# 5V_Inputs.net
KiCad netlist of a schematic drawn in Altium Designer
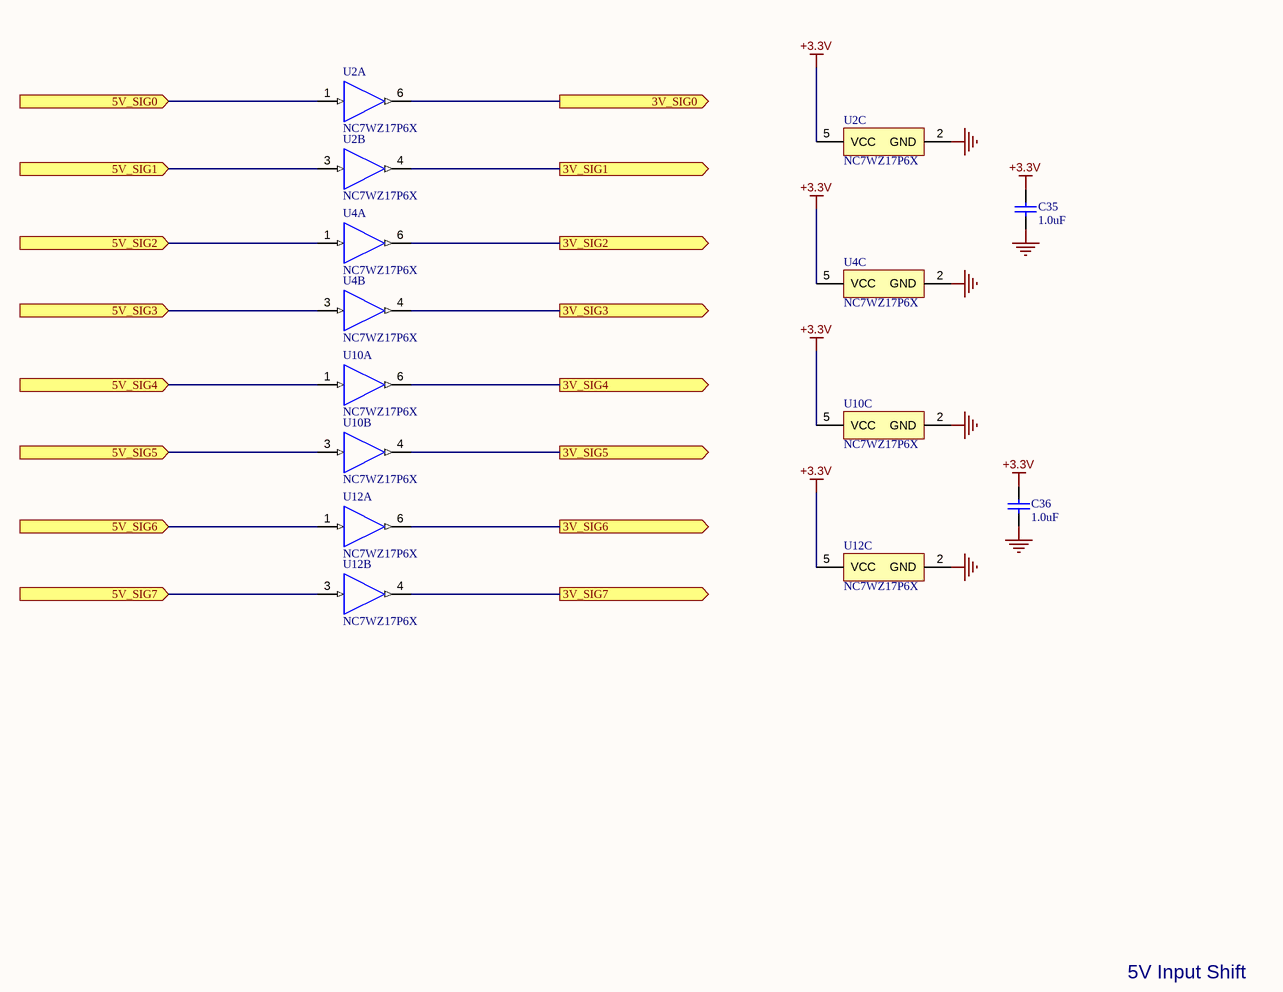
[diagram p0: 5V_Inputs.SchDoc]

(export (version "E")
  (design (tool "Eeschema 10.0.6"))
  (components
    (comp (ref "C35")
      (value "1.0uF")
      (footprint "0402_C")
      (description "Chip capacitor")
      (fields
        (field (name "MANUFACTURER") "Samsung Electro-Mechanics")
        (field (name "PARTNUMBER") "CL05A105KA5NQNC")
      )
      (libsource (lib "Cap") (part "0402 1.0uF (105) 10% 25V"))
    )
    (comp (ref "C36")
      (value "1.0uF")
      (footprint "0402_C")
      (description "Chip capacitor")
      (fields
        (field (name "MANUFACTURER") "Samsung Electro-Mechanics")
        (field (name "PARTNUMBER") "CL05A105KA5NQNC")
      )
      (libsource (lib "Cap") (part "0402 1.0uF (105) 10% 25V"))
    )
    (comp (ref "U2")
      (value "NC7WZ17P6X")
      (footprint "FAIR-SC70-6_V")
      (fields (field (name "MANUFACTURER") "Fairchild Semiconductor"))
      (libsource (lib "Altium Content Vault") (part "BUFFER-2-1IN-6"))
    )
    (comp (ref "U4")
      (value "NC7WZ17P6X")
      (footprint "FAIR-SC70-6_V")
      (fields (field (name "MANUFACTURER") "Fairchild Semiconductor"))
      (libsource (lib "Altium Content Vault") (part "BUFFER-2-1IN-6"))
    )
    (comp (ref "U10")
      (value "NC7WZ17P6X")
      (footprint "FAIR-SC70-6_V")
      (fields (field (name "MANUFACTURER") "Fairchild Semiconductor"))
      (libsource (lib "Altium Content Vault") (part "BUFFER-2-1IN-6"))
    )
    (comp (ref "U12")
      (value "NC7WZ17P6X")
      (footprint "FAIR-SC70-6_V")
      (fields (field (name "MANUFACTURER") "Fairchild Semiconductor"))
      (libsource (lib "Altium Content Vault") (part "BUFFER-2-1IN-6"))
    )
  )
  (nets
    (net (code "1") (name "+3.3V") (class "Default")
      (node (ref "C35") (pin "1") (pinfunction "1_1") (pintype "passive"))
      (node (ref "C36") (pin "1") (pinfunction "1_1") (pintype "passive"))
      (node (ref "U10") (pin "5") (pinfunction "VCC_5") (pintype "power_in"))
      (node (ref "U12") (pin "5") (pinfunction "VCC_5") (pintype "power_in"))
      (node (ref "U2") (pin "5") (pinfunction "VCC_5") (pintype "power_in"))
      (node (ref "U4") (pin "5") (pinfunction "VCC_5") (pintype "power_in"))
    )
    (net (code "2") (name "/3V_SIG0") (class "Default")
      (node (ref "U2") (pin "6") (pinfunction "Y1_6") (pintype "output"))
    )
    (net (code "3") (name "/3V_SIG1") (class "Default")
      (node (ref "U2") (pin "4") (pinfunction "Y2_4") (pintype "output"))
    )
    (net (code "4") (name "/3V_SIG2") (class "Default")
      (node (ref "U4") (pin "6") (pinfunction "Y1_6") (pintype "output"))
    )
    (net (code "5") (name "/3V_SIG3") (class "Default")
      (node (ref "U4") (pin "4") (pinfunction "Y2_4") (pintype "output"))
    )
    (net (code "6") (name "/3V_SIG4") (class "Default")
      (node (ref "U10") (pin "6") (pinfunction "Y1_6") (pintype "output"))
    )
    (net (code "7") (name "/3V_SIG5") (class "Default")
      (node (ref "U10") (pin "4") (pinfunction "Y2_4") (pintype "output"))
    )
    (net (code "8") (name "/3V_SIG6") (class "Default")
      (node (ref "U12") (pin "6") (pinfunction "Y1_6") (pintype "output"))
    )
    (net (code "9") (name "/3V_SIG7") (class "Default")
      (node (ref "U12") (pin "4") (pinfunction "Y2_4") (pintype "output"))
    )
    (net (code "10") (name "/5V_SIG0") (class "Default")
      (node (ref "U2") (pin "1") (pinfunction "A1_1") (pintype "input"))
    )
    (net (code "11") (name "/5V_SIG1") (class "Default")
      (node (ref "U2") (pin "3") (pinfunction "A2_3") (pintype "input"))
    )
    (net (code "12") (name "/5V_SIG2") (class "Default")
      (node (ref "U4") (pin "1") (pinfunction "A1_1") (pintype "input"))
    )
    (net (code "13") (name "/5V_SIG3") (class "Default")
      (node (ref "U4") (pin "3") (pinfunction "A2_3") (pintype "input"))
    )
    (net (code "14") (name "/5V_SIG4") (class "Default")
      (node (ref "U10") (pin "1") (pinfunction "A1_1") (pintype "input"))
    )
    (net (code "15") (name "/5V_SIG5") (class "Default")
      (node (ref "U10") (pin "3") (pinfunction "A2_3") (pintype "input"))
    )
    (net (code "16") (name "/5V_SIG6") (class "Default")
      (node (ref "U12") (pin "1") (pinfunction "A1_1") (pintype "input"))
    )
    (net (code "17") (name "/5V_SIG7") (class "Default")
      (node (ref "U12") (pin "3") (pinfunction "A2_3") (pintype "input"))
    )
    (net (code "18") (name "GND") (class "Default")
      (node (ref "C35") (pin "2") (pinfunction "2_2") (pintype "passive"))
      (node (ref "C36") (pin "2") (pinfunction "2_2") (pintype "passive"))
      (node (ref "U10") (pin "2") (pinfunction "GND_2") (pintype "power_in"))
      (node (ref "U12") (pin "2") (pinfunction "GND_2") (pintype "power_in"))
      (node (ref "U2") (pin "2") (pinfunction "GND_2") (pintype "power_in"))
      (node (ref "U4") (pin "2") (pinfunction "GND_2") (pintype "power_in"))
    )
  )
)
